# Sudden_XCVF_Transmit_Pre-Driver_Stage.net
KiCad netlist of a schematic drawn in EAGLE
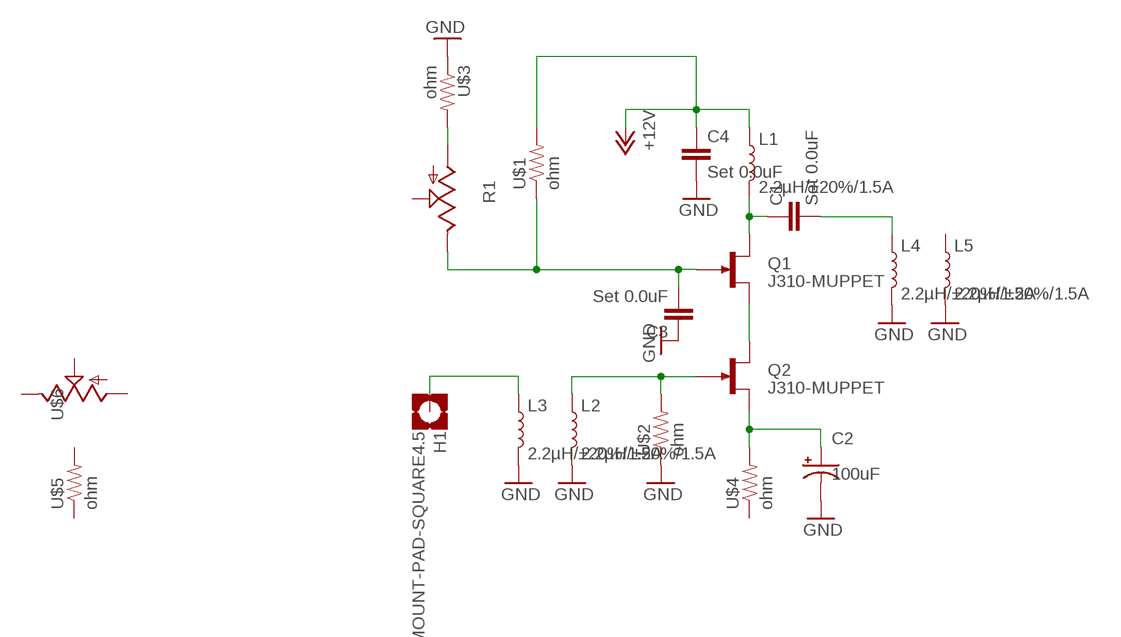
[diagram p0: schematic, sheet 1]

(export (version "E")
  (design (tool "Eeschema 10.0.6"))
  (components
    (comp (ref "C1")
      (value "Set 0.0uF")
      (footprint "eagle-import:CAP-MEDIUM-MUPPET")
      (libsource (lib "eagle-import") (part "CAP-MEDIUM-MUPPET"))
    )
    (comp (ref "C2")
      (value "100uF")
      (footprint "eagle-import:CAP-POLARIZED")
      (libsource (lib "eagle-import") (part "CAP-POLARIZED-RADIAL-2.5MM-25V-20%"))
    )
    (comp (ref "C3")
      (value "Set 0.0uF")
      (footprint "eagle-import:CAP-MEDIUM-MUPPET")
      (libsource (lib "eagle-import") (part "CAP-MEDIUM-MUPPET"))
    )
    (comp (ref "C4")
      (value "Set 0.0uF")
      (footprint "eagle-import:CAP-MEDIUM-MUPPET")
      (libsource (lib "eagle-import") (part "CAP-MEDIUM-MUPPET"))
    )
    (comp (ref "H1")
      (value "MOUNT-PAD-SQUARE4.5")
      (footprint "eagle-import:PAD-SQUARE")
      (libsource (lib "eagle-import") (part "MOUNT-PAD-SQUARE4.5"))
    )
    (comp (ref "L1")
      (value "2.2µH/±20%/1.5A")
      (footprint "eagle-import:INDUCTOR_2.2UH")
      (libsource (lib "eagle-import") (part "INDUCTOR-VLF4012AT-2.2UH"))
    )
    (comp (ref "L2")
      (value "2.2µH/±20%/1.5A")
      (footprint "eagle-import:INDUCTOR_2.2UH")
      (libsource (lib "eagle-import") (part "INDUCTOR-VLF4012AT-2.2UH"))
    )
    (comp (ref "L3")
      (value "2.2µH/±20%/1.5A")
      (footprint "eagle-import:INDUCTOR_2.2UH")
      (libsource (lib "eagle-import") (part "INDUCTOR-VLF4012AT-2.2UH"))
    )
    (comp (ref "L4")
      (value "2.2µH/±20%/1.5A")
      (footprint "eagle-import:INDUCTOR_2.2UH")
      (libsource (lib "eagle-import") (part "INDUCTOR-VLF4012AT-2.2UH"))
    )
    (comp (ref "L5")
      (value "2.2µH/±20%/1.5A")
      (footprint "eagle-import:INDUCTOR_2.2UH")
      (libsource (lib "eagle-import") (part "INDUCTOR-VLF4012AT-2.2UH"))
    )
    (comp (ref "P+1")
      (value "+12V")
      (footprint "eagle-import:POWER-IN-PAD")
      (libsource (lib "eagle-import") (part "+12V"))
    )
    (comp (ref "Q1")
      (value "J310-MUPPET")
      (footprint "eagle-import:TO92R-MUPPET")
      (libsource (lib "eagle-import") (part "J310-MUPPET"))
    )
    (comp (ref "Q2")
      (value "J310-MUPPET")
      (footprint "eagle-import:TO92R-MUPPET")
      (libsource (lib "eagle-import") (part "J310-MUPPET"))
    )
    (comp (ref "R1")
      (value "POTENTIOMETER-TRIMCT6")
      (footprint "eagle-import:POT-TRIMM-4")
      (libsource (lib "eagle-import") (part "POTENTIOMETER-TRIMCT6"))
    )
    (comp (ref "U$1")
      (value "ohm")
      (footprint "eagle-import:RESITOR-MUPPET")
      (libsource (lib "eagle-import") (part "RESISTOR-MUPPETMEDIUM-RESISTOR-PADS"))
    )
    (comp (ref "U$2")
      (value "ohm")
      (footprint "eagle-import:RESITOR-MUPPET")
      (libsource (lib "eagle-import") (part "RESISTOR-MUPPETMEDIUM-RESISTOR-PADS"))
    )
    (comp (ref "U$3")
      (value "ohm")
      (footprint "eagle-import:RESITOR-MUPPET")
      (libsource (lib "eagle-import") (part "RESISTOR-MUPPETMEDIUM-RESISTOR-PADS"))
    )
    (comp (ref "U$4")
      (value "ohm")
      (footprint "eagle-import:RESITOR-MUPPET")
      (libsource (lib "eagle-import") (part "RESISTOR-MUPPETMEDIUM-RESISTOR-PADS"))
    )
    (comp (ref "U$5")
      (value "ohm")
      (footprint "eagle-import:RESITOR-MUPPET")
      (libsource (lib "eagle-import") (part "RESISTOR-MUPPETMEDIUM-RESISTOR-PADS"))
    )
    (comp (ref "U$6")
      (value "ohm")
      (footprint "eagle-import:POT-TRIMM-4")
      (libsource (lib "eagle-import") (part "POTENTIOMETER-TRIMCT6"))
    )
  )
  (nets
    (net (code "1") (name "+12V") (class "Default")
      (node (ref "C4") (pin "1") (pinfunction "1_1") (pintype "passive"))
      (node (ref "L1") (pin "P$1") (pinfunction "1_P$1") (pintype "passive"))
      (node (ref "P+1") (pin "VCC") (pinfunction "+12V_VCC") (pintype "power_in"))
      (node (ref "U$1") (pin "P$2") (pinfunction "2_P$2") (pintype "passive"))
    )
    (net (code "2") (name "GND") (class "Default")
      (node (ref "C2") (pin "2") (pinfunction "-_2") (pintype "passive"))
      (node (ref "C3") (pin "1") (pinfunction "1_1") (pintype "passive"))
      (node (ref "C4") (pin "2") (pinfunction "2_2") (pintype "passive"))
      (node (ref "L2") (pin "P$2") (pinfunction "2_P$2") (pintype "passive"))
      (node (ref "L3") (pin "P$2") (pinfunction "2_P$2") (pintype "passive"))
      (node (ref "L4") (pin "P$2") (pinfunction "2_P$2") (pintype "passive"))
      (node (ref "L5") (pin "P$2") (pinfunction "2_P$2") (pintype "passive"))
      (node (ref "U$2") (pin "P$1") (pinfunction "1_P$1") (pintype "passive"))
      (node (ref "U$3") (pin "P$1") (pinfunction "1_P$1") (pintype "passive"))
    )
    (net (code "3") (name "Net-(C2-+)") (class "Default")
      (node (ref "C2") (pin "1") (pinfunction "+_1") (pintype "passive"))
      (node (ref "Q2") (pin "S") (pinfunction "S_S") (pintype "passive"))
      (node (ref "U$4") (pin "P$2") (pinfunction "2_P$2") (pintype "passive"))
    )
    (net (code "4") (name "Net-(H1-MOUNT)") (class "Default")
      (node (ref "H1") (pin "PAD") (pinfunction "MOUNT_PAD") (pintype "passive"))
      (node (ref "L3") (pin "P$1") (pinfunction "1_P$1") (pintype "passive"))
    )
    (net (code "5") (name "Net-(L1-2)") (class "Default")
      (node (ref "C1") (pin "1") (pinfunction "1_1") (pintype "passive"))
      (node (ref "L1") (pin "P$2") (pinfunction "2_P$2") (pintype "passive"))
      (node (ref "Q1") (pin "D") (pinfunction "D_D") (pintype "passive"))
    )
    (net (code "6") (name "Net-(L2-1)") (class "Default")
      (node (ref "L2") (pin "P$1") (pinfunction "1_P$1") (pintype "passive"))
      (node (ref "Q2") (pin "G") (pinfunction "G_G") (pintype "passive"))
      (node (ref "U$2") (pin "P$2") (pinfunction "2_P$2") (pintype "passive"))
    )
    (net (code "7") (name "Net-(L4-1)") (class "Default")
      (node (ref "C1") (pin "2") (pinfunction "2_2") (pintype "passive"))
      (node (ref "L4") (pin "P$1") (pinfunction "1_P$1") (pintype "passive"))
    )
    (net (code "8") (name "Net-(Q1-PadS)") (class "Default")
      (node (ref "Q1") (pin "S") (pinfunction "S_S") (pintype "passive"))
      (node (ref "Q2") (pin "D") (pinfunction "D_D") (pintype "passive"))
    )
    (net (code "9") (name "Net-(U$1-1)") (class "Default")
      (node (ref "C3") (pin "2") (pinfunction "2_2") (pintype "passive"))
      (node (ref "Q1") (pin "G") (pinfunction "G_G") (pintype "passive"))
      (node (ref "R1") (pin "E") (pinfunction "E_E") (pintype "passive"))
      (node (ref "U$1") (pin "P$1") (pinfunction "1_P$1") (pintype "passive"))
    )
    (net (code "10") (name "Net-(U$3-2)") (class "Default")
      (node (ref "R1") (pin "A") (pinfunction "A_A") (pintype "passive"))
      (node (ref "U$3") (pin "P$2") (pinfunction "2_P$2") (pintype "passive"))
    )
    (net (code "11") (name "unconnected-(L5-1-PadP$1)") (class "Default")
      (node (ref "L5") (pin "P$1") (pinfunction "1_P$1") (pintype "passive"))
    )
    (net (code "12") (name "unconnected-(R1-PadS)") (class "Default")
      (node (ref "R1") (pin "S") (pinfunction "S_S") (pintype "passive"))
    )
    (net (code "13") (name "unconnected-(U$4-1-PadP$1)") (class "Default")
      (node (ref "U$4") (pin "P$1") (pinfunction "1_P$1") (pintype "passive"))
    )
    (net (code "14") (name "unconnected-(U$5-1-PadP$1)") (class "Default")
      (node (ref "U$5") (pin "P$1") (pinfunction "1_P$1") (pintype "passive"))
    )
    (net (code "15") (name "unconnected-(U$5-2-PadP$2)") (class "Default")
      (node (ref "U$5") (pin "P$2") (pinfunction "2_P$2") (pintype "passive"))
    )
    (net (code "16") (name "unconnected-(U$6-PadA)") (class "Default")
      (node (ref "U$6") (pin "A") (pinfunction "A_A") (pintype "passive"))
    )
    (net (code "17") (name "unconnected-(U$6-PadE)") (class "Default")
      (node (ref "U$6") (pin "E") (pinfunction "E_E") (pintype "passive"))
    )
    (net (code "18") (name "unconnected-(U$6-PadS)") (class "Default")
      (node (ref "U$6") (pin "S") (pinfunction "S_S") (pintype "passive"))
    )
  )
)
